# AudioFrontend.net
KiCad netlist of a schematic drawn in Altium Designer
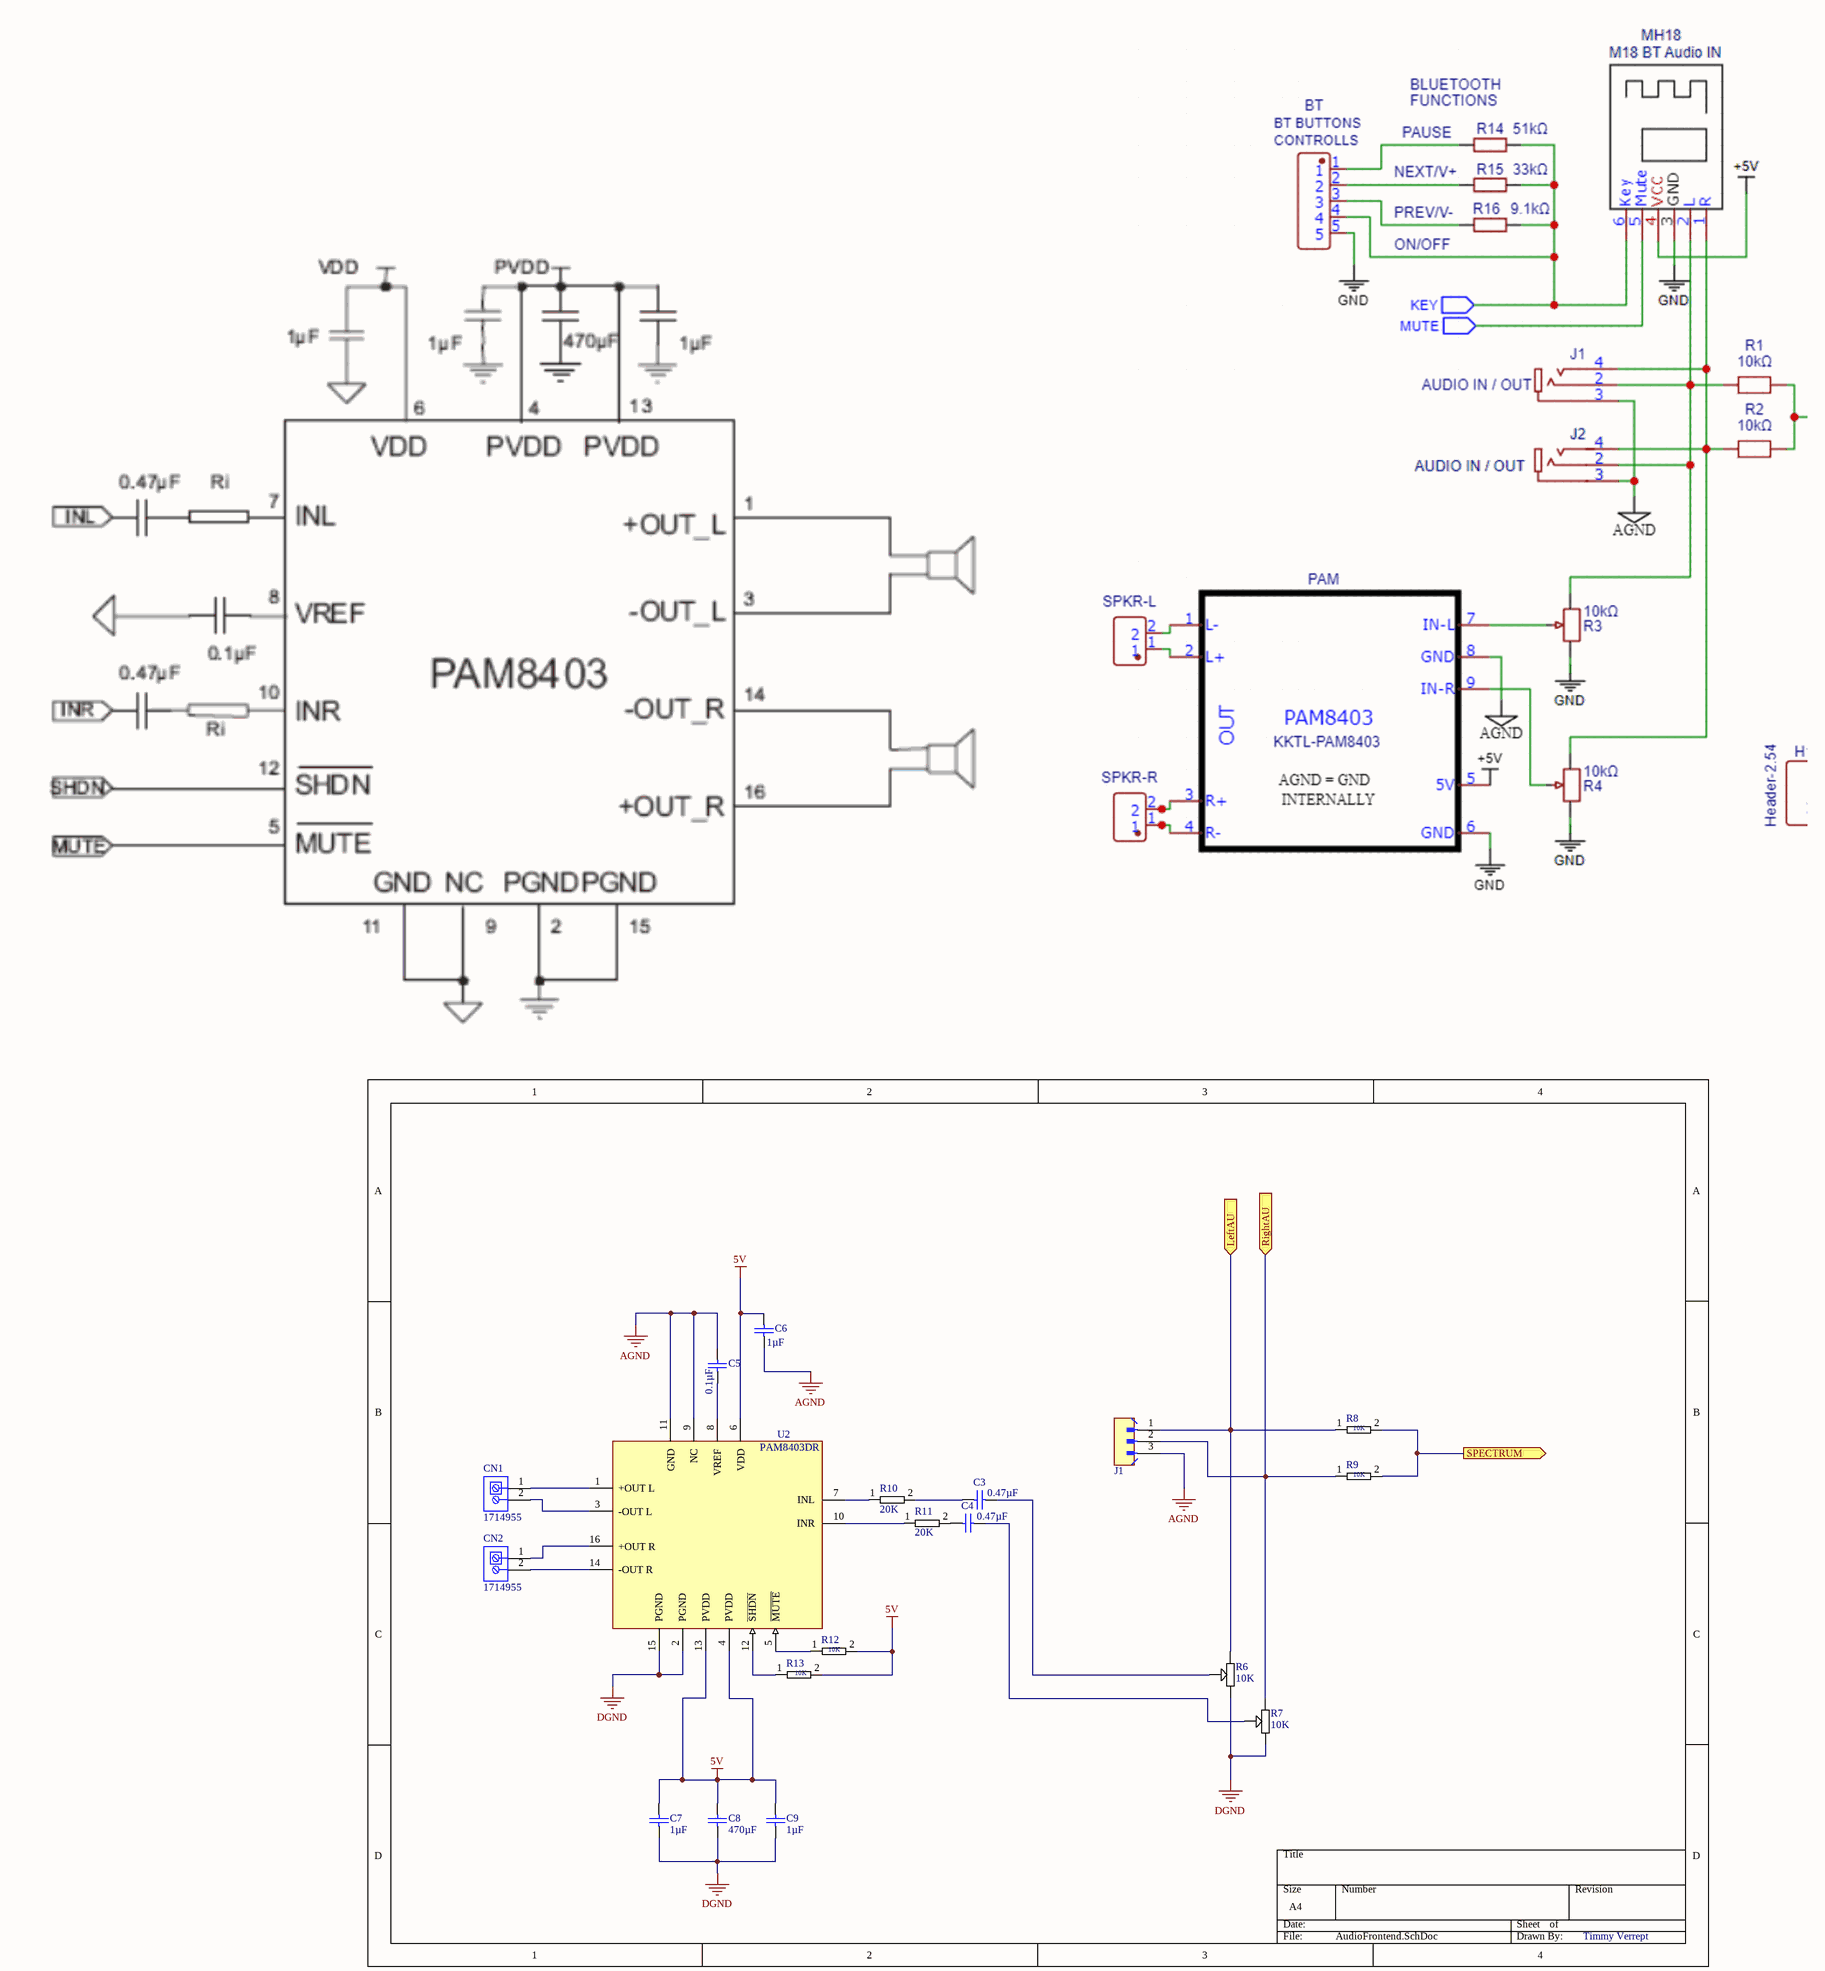
[diagram p0: AudioFrontend.SchDoc]

(export (version "E")
  (design (tool "Eeschema 10.0.6"))
  (components
    (comp (ref "C3")
      (value "0.47µF")
      (footprint "SMD_CAPACITOR")
      (fields (field (name "MANUFACTURER") "Vitramon") (field (name "PART NUMBER") "VJ0805Y682KXAMT"))
      (libsource (lib "Winnetrie_library") (part "CER Capacitor"))
    )
    (comp (ref "C4")
      (value "0.47µF")
      (footprint "SMD_CAPACITOR")
      (fields (field (name "MANUFACTURER") "Vitramon") (field (name "PART NUMBER") "VJ0805Y682KXAMT"))
      (libsource (lib "Winnetrie_library") (part "CER Capacitor"))
    )
    (comp (ref "C5")
      (value "0.1µF")
      (footprint "SMD_CAPACITOR")
      (fields (field (name "MANUFACTURER") "Vitramon") (field (name "PART NUMBER") "VJ0805Y682KXAMT"))
      (libsource (lib "Winnetrie_library") (part "CER Capacitor"))
    )
    (comp (ref "C6")
      (value "1µF")
      (footprint "SMD_CAPACITOR")
      (fields (field (name "MANUFACTURER") "Vitramon") (field (name "PART NUMBER") "VJ0805Y682KXAMT"))
      (libsource (lib "Winnetrie_library") (part "CER Capacitor"))
    )
    (comp (ref "C7")
      (value "1µF")
      (footprint "SMD_CAPACITOR")
      (fields (field (name "MANUFACTURER") "Vitramon") (field (name "PART NUMBER") "VJ0805Y682KXAMT"))
      (libsource (lib "Winnetrie_library") (part "CER Capacitor"))
    )
    (comp (ref "C8")
      (value "470µF")
      (footprint "SMD_CAPACITOR")
      (fields (field (name "MANUFACTURER") "Vitramon") (field (name "PART NUMBER") "VJ0805Y682KXAMT"))
      (libsource (lib "Winnetrie_library") (part "CER Capacitor"))
    )
    (comp (ref "C9")
      (value "1µF")
      (footprint "SMD_CAPACITOR")
      (fields (field (name "MANUFACTURER") "Vitramon") (field (name "PART NUMBER") "VJ0805Y682KXAMT"))
      (libsource (lib "Winnetrie_library") (part "CER Capacitor"))
    )
    (comp (ref "CN1")
      (value "1714955")
      (footprint "SchroefConnector2P")
      (description "PC Terminal Block, Pitch 6.35 mm, 1 x 2 Position, Height 21.5 mm, Tail Lenght 5.1 mm, RoHS, Bulk")
      (fields (field (name "MANUFACTURER") "Phoenix Contact"))
      (libsource (lib "Winnetrie_library") (part "schroefconnector 2 pins"))
    )
    (comp (ref "CN2")
      (value "1714955")
      (footprint "SchroefConnector2P")
      (description "PC Terminal Block, Pitch 6.35 mm, 1 x 2 Position, Height 21.5 mm, Tail Lenght 5.1 mm, RoHS, Bulk")
      (fields (field (name "MANUFACTURER") "Phoenix Contact"))
      (libsource (lib "Winnetrie_library") (part "schroefconnector 2 pins"))
    )
    (comp (ref "J1")
      (value "B3B-PH-K-S")
      (footprint "Connector3P")
      (fields (field (name "MF") "{'manufacturer': u'JST Sales America Inc.'}"))
      (libsource (lib "Winnetrie_library") (part "Connector_3p"))
    )
    (comp (ref "R6")
      (value "10K")
      (footprint "POTENTIOMETER")
      (description "16mm Rotary Potentiometers\r\nWH148-1A-2-18T-L20")
      (fields (field (name "MF") "Kls electronics") (field (name "MP") "WH148-1A-2-18T-L20"))
      (libsource (lib "Winnetrie_library") (part "Potmeter"))
    )
    (comp (ref "R7")
      (value "10K")
      (footprint "POTENTIOMETER")
      (description "16mm Rotary Potentiometers\r\nWH148-1A-2-18T-L20")
      (fields (field (name "MF") "Kls electronics") (field (name "MP") "WH148-1A-2-18T-L20"))
      (libsource (lib "Winnetrie_library") (part "Potmeter"))
    )
    (comp (ref "R8")
      (value "10K")
      (footprint "SMD_RESISTOR")
      (description "RES SMD 681 OHM 0.1% 1/8W 0805")
      (fields
        (field (name "MANUFACTURER") "Yageo")
        (field (name "MANUFACTURER PART NUMBER") "RT0805BRD07681RL")
      )
      (libsource (lib "Winnetrie_library") (part "Resistor"))
    )
    (comp (ref "R9")
      (value "10K")
      (footprint "SMD_RESISTOR")
      (description "RES SMD 681 OHM 0.1% 1/8W 0805")
      (fields
        (field (name "MANUFACTURER") "Yageo")
        (field (name "MANUFACTURER PART NUMBER") "RT0805BRD07681RL")
      )
      (libsource (lib "Winnetrie_library") (part "Resistor"))
    )
    (comp (ref "R10")
      (value "20K")
      (footprint "SMD_RESISTOR")
      (description "RES SMD 681 OHM 0.1% 1/8W 0805")
      (fields
        (field (name "MANUFACTURER") "Yageo")
        (field (name "MANUFACTURER PART NUMBER") "RT0805BRD07681RL")
      )
      (libsource (lib "Winnetrie_library") (part "Resistor"))
    )
    (comp (ref "R11")
      (value "20K")
      (footprint "SMD_RESISTOR")
      (description "RES SMD 681 OHM 0.1% 1/8W 0805")
      (fields
        (field (name "MANUFACTURER") "Yageo")
        (field (name "MANUFACTURER PART NUMBER") "RT0805BRD07681RL")
      )
      (libsource (lib "Winnetrie_library") (part "Resistor"))
    )
    (comp (ref "R12")
      (value "10K")
      (footprint "SMD_RESISTOR")
      (description "RES SMD 681 OHM 0.1% 1/8W 0805")
      (fields
        (field (name "MANUFACTURER") "Yageo")
        (field (name "MANUFACTURER PART NUMBER") "RT0805BRD07681RL")
      )
      (libsource (lib "Winnetrie_library") (part "Resistor"))
    )
    (comp (ref "R13")
      (value "10K")
      (footprint "SMD_RESISTOR")
      (description "RES SMD 681 OHM 0.1% 1/8W 0805")
      (fields
        (field (name "MANUFACTURER") "Yageo")
        (field (name "MANUFACTURER PART NUMBER") "RT0805BRD07681RL")
      )
      (libsource (lib "Winnetrie_library") (part "Resistor"))
    )
    (comp (ref "U2")
      (value "PAM8403DR")
      (footprint "PAM8403")
      (description "IC AMP CLASS D STEREO 3W 16SOP")
      (fields
        (field (name "MANUFACTURER") "Diodes Inc.")
        (field (name "OCTOPART") "https://octopart.com/pam8403dr-diodes+inc.-29030487")
      )
      (libsource (lib "Winnetrie_library") (part "Pam8403"))
    )
  )
  (nets
    (net (code "1") (name "/LeftAU") (class "Default")
      (node (ref "J1") (pin "1") (pinfunction "1_1") (pintype "passive"))
      (node (ref "R6") (pin "1") (pinfunction "1_1") (pintype "passive"))
      (node (ref "R8") (pin "1") (pinfunction "1_1") (pintype "passive"))
    )
    (net (code "2") (name "/RightAU") (class "Default")
      (node (ref "J1") (pin "2") (pinfunction "2_2") (pintype "passive"))
      (node (ref "R7") (pin "1") (pinfunction "1_1") (pintype "passive"))
      (node (ref "R9") (pin "1") (pinfunction "1_1") (pintype "passive"))
    )
    (net (code "3") (name "/SPECTRUM") (class "Default")
      (node (ref "R8") (pin "2") (pinfunction "2_2") (pintype "passive"))
      (node (ref "R9") (pin "2") (pinfunction "2_2") (pintype "passive"))
    )
    (net (code "4") (name "5V") (class "Default")
      (node (ref "C6") (pin "1") (pinfunction "1_1") (pintype "passive"))
      (node (ref "C7") (pin "1") (pinfunction "1_1") (pintype "passive"))
      (node (ref "C8") (pin "1") (pinfunction "1_1") (pintype "passive"))
      (node (ref "C9") (pin "1") (pinfunction "1_1") (pintype "passive"))
      (node (ref "R12") (pin "2") (pinfunction "2_2") (pintype "passive"))
      (node (ref "R13") (pin "2") (pinfunction "2_2") (pintype "passive"))
      (node (ref "U2") (pin "13") (pinfunction "PVDD_13") (pintype "power_in"))
      (node (ref "U2") (pin "4") (pinfunction "PVDD_4") (pintype "power_in"))
      (node (ref "U2") (pin "6") (pinfunction "VDD_6") (pintype "power_in"))
    )
    (net (code "5") (name "AGND") (class "Default")
      (node (ref "C5") (pin "1") (pinfunction "1_1") (pintype "passive"))
      (node (ref "C6") (pin "2") (pinfunction "2_2") (pintype "passive"))
      (node (ref "J1") (pin "3") (pinfunction "3_3") (pintype "passive"))
      (node (ref "U2") (pin "11") (pinfunction "GND_11") (pintype "power_in"))
      (node (ref "U2") (pin "9") (pinfunction "NC_9") (pintype "passive"))
    )
    (net (code "6") (name "DGND") (class "Default")
      (node (ref "C7") (pin "2") (pinfunction "2_2") (pintype "passive"))
      (node (ref "C8") (pin "2") (pinfunction "2_2") (pintype "passive"))
      (node (ref "C9") (pin "2") (pinfunction "2_2") (pintype "passive"))
      (node (ref "R6") (pin "3") (pinfunction "3_3") (pintype "passive"))
      (node (ref "R7") (pin "3") (pinfunction "3_3") (pintype "passive"))
      (node (ref "U2") (pin "15") (pinfunction "PGND_15") (pintype "power_in"))
      (node (ref "U2") (pin "2") (pinfunction "PGND_2") (pintype "power_in"))
    )
    (net (code "7") (name "Net-(C3-Pad1)") (class "Default")
      (node (ref "C3") (pin "1") (pinfunction "1_1") (pintype "passive"))
      (node (ref "R10") (pin "2") (pinfunction "2_2") (pintype "passive"))
    )
    (net (code "8") (name "Net-(C3-Pad2)") (class "Default")
      (node (ref "C3") (pin "2") (pinfunction "2_2") (pintype "passive"))
      (node (ref "R6") (pin "2") (pinfunction "2_2") (pintype "passive"))
    )
    (net (code "9") (name "Net-(C4-Pad1)") (class "Default")
      (node (ref "C4") (pin "1") (pinfunction "1_1") (pintype "passive"))
      (node (ref "R11") (pin "2") (pinfunction "2_2") (pintype "passive"))
    )
    (net (code "10") (name "Net-(C4-Pad2)") (class "Default")
      (node (ref "C4") (pin "2") (pinfunction "2_2") (pintype "passive"))
      (node (ref "R7") (pin "2") (pinfunction "2_2") (pintype "passive"))
    )
    (net (code "11") (name "Net-(U2-+OUT_L)") (class "Default")
      (node (ref "CN1") (pin "1") (pinfunction "1_1") (pintype "passive"))
      (node (ref "U2") (pin "1") (pinfunction "+OUT_L_1") (pintype "passive"))
    )
    (net (code "12") (name "Net-(U2-+OUT_R)") (class "Default")
      (node (ref "CN2") (pin "1") (pinfunction "1_1") (pintype "passive"))
      (node (ref "U2") (pin "16") (pinfunction "+OUT_R_16") (pintype "passive"))
    )
    (net (code "13") (name "Net-(U2--OUT_L)") (class "Default")
      (node (ref "CN1") (pin "2") (pinfunction "2_2") (pintype "passive"))
      (node (ref "U2") (pin "3") (pinfunction "-OUT_L_3") (pintype "passive"))
    )
    (net (code "14") (name "Net-(U2--OUT_R)") (class "Default")
      (node (ref "CN2") (pin "2") (pinfunction "2_2") (pintype "passive"))
      (node (ref "U2") (pin "14") (pinfunction "-OUT_R_14") (pintype "passive"))
    )
    (net (code "15") (name "Net-(U2-INL)") (class "Default")
      (node (ref "R10") (pin "1") (pinfunction "1_1") (pintype "passive"))
      (node (ref "U2") (pin "7") (pinfunction "INL_7") (pintype "passive"))
    )
    (net (code "16") (name "Net-(U2-INR)") (class "Default")
      (node (ref "R11") (pin "1") (pinfunction "1_1") (pintype "passive"))
      (node (ref "U2") (pin "10") (pinfunction "INR_10") (pintype "passive"))
    )
    (net (code "17") (name "Net-(U2-VREF)") (class "Default")
      (node (ref "C5") (pin "2") (pinfunction "2_2") (pintype "passive"))
      (node (ref "U2") (pin "8") (pinfunction "VREF_8") (pintype "passive"))
    )
    (net (code "18") (name "Net-(U2-~{MUTE})") (class "Default")
      (node (ref "R12") (pin "1") (pinfunction "1_1") (pintype "passive"))
      (node (ref "U2") (pin "5") (pinfunction "~{MUTE}_5") (pintype "input"))
    )
    (net (code "19") (name "Net-(U2-~{SHDN})") (class "Default")
      (node (ref "R13") (pin "1") (pinfunction "1_1") (pintype "passive"))
      (node (ref "U2") (pin "12") (pinfunction "~{SHDN}_12") (pintype "input"))
    )
  )
)
